# Pedal_SD_USB.net
KiCad netlist of a schematic drawn in Altium Designer
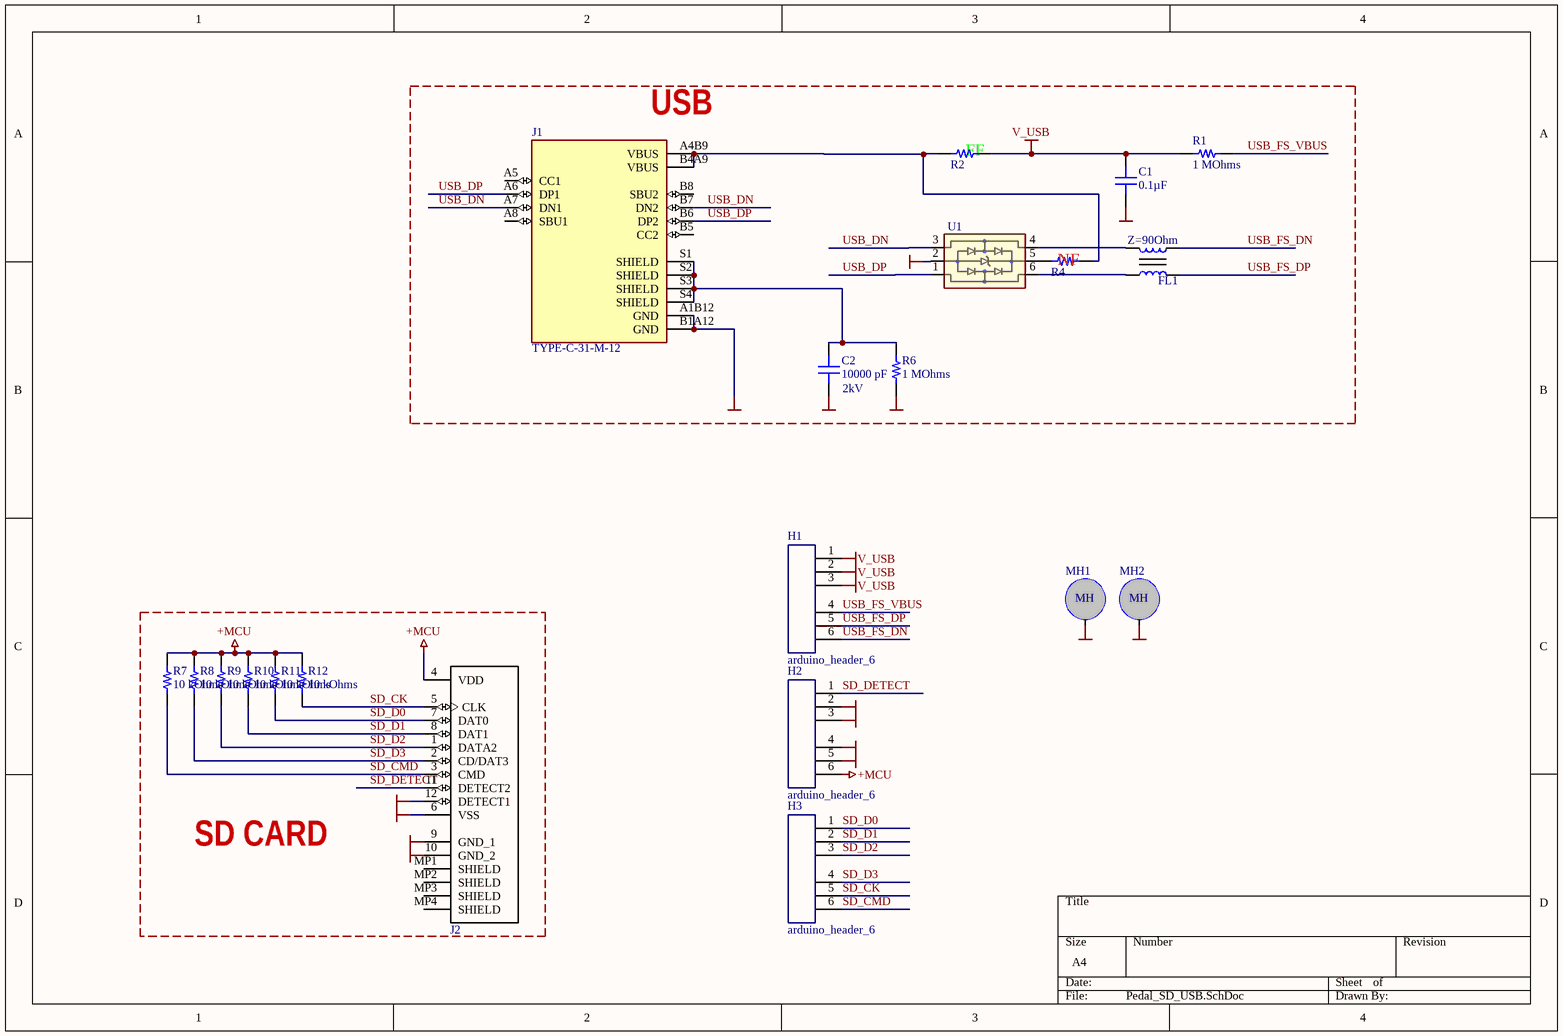
[diagram p0: Pedal_SD_USB.SchDoc]

(export (version "E")
  (design (tool "Eeschema 10.0.6"))
  (components
    (comp (ref "C1")
      (value "0.1µF")
      (footprint "CAP 0402_1005")
      (description "CAP CER 0.1UF 16V X7R 0402")
      (fields (field (name "PART NUMBER") "C0402C104K4RACAUTO") (field (name "MANUFACTURER") "KEMET"))
      (libsource (lib "Celestial Altium Library - altium_library") (part "Capacitor"))
    )
    (comp (ref "C2")
      (value "10000 pF")
      (footprint "CAP 1210_3225 - 1MM")
      (description "CAP CER 10000PF 1KV X7R 1210")
      (fields (field (name "PART NUMBER") "C1210C103KDRAC7800") (field (name "MANUFACTURER") "KEMET"))
      (libsource (lib "Celestial Altium Library - altium_library") (part "Capacitor"))
    )
    (comp (ref "FL1")
      (value "Z=90Ohm")
      (footprint "ProtoStack_H750VBT:FIL_ACM2012-361-2P-T002")
      (description "ACM Series 0805 360 Ohm 220mA 500 mOhm DCR 50 V SMT Common Mode Filter")
      (fields (field (name "MP") "ACM2012-361-2P-T002") (field (name "MF") "TDK"))
      (libsource (lib "ProtoStack_H750VBT") (part "ACM2012-361-2P-T002"))
    )
    (comp (ref "H1")
      (value "arduino_header_6")
      (footprint "ProtoStack_H750VBT:header-6_male")
      (libsource (lib "ProtoStack_H750VBT") (part "arduino_header_6"))
    )
    (comp (ref "H2")
      (value "arduino_header_6")
      (footprint "ProtoStack_H750VBT:header-6_male")
      (libsource (lib "ProtoStack_H750VBT") (part "arduino_header_6"))
    )
    (comp (ref "H3")
      (value "arduino_header_6")
      (footprint "ProtoStack_H750VBT:header-6_male")
      (libsource (lib "ProtoStack_H750VBT") (part "arduino_header_6"))
    )
    (comp (ref "J1")
      (value "TYPE-C-31-M-12")
      (footprint "ProtoStack_H750VBT:HRO_TYPE-C-31-M-12 - REZONIT")
      (description "USB Connectors 24 Receptacle 1 8.94*7.3mm RoHS")
      (fields (field (name "MF") "{'manufacturer': u'HRO Electronics Co., Ltd.'}"))
      (libsource (lib "ProtoStack_H750VBT") (part "TYPE-C-31-M-12"))
    )
    (comp (ref "J2")
      (value "SCHA4B0400")
      (footprint "ProtoStack_H750VBT:SCHA4B0400")
      (description "SD card Connector")
      (fields (field (name "MOUSER PART NUMBER") "688-SCHA4B0400"))
      (libsource (lib "ProtoStack_H750VBT") (part "SCHA4B0400"))
    )
    (comp (ref "MH1")
      (value "MountingHole")
      (footprint "ProtoStack_H750VBT:Hole_2.5mm")
      (libsource (lib "ProtoStack_H750VBT") (part "MountingHole"))
    )
    (comp (ref "MH2")
      (value "MountingHole")
      (footprint "ProtoStack_H750VBT:Hole_2.5mm")
      (libsource (lib "ProtoStack_H750VBT") (part "MountingHole"))
    )
    (comp (ref "R1")
      (value "1 MOhms")
      (footprint "RES 0603_1608")
      (description "RES SMD 1M OHM 1% 1/10W 0603")
      (fields
        (field (name "PART NUMBER") "ERJ-3EKF1004V")
        (field (name "MANUFACTURER") "Panasonic Electronic Components")
      )
      (libsource (lib "Celestial Altium Library - altium_library") (part "Resistor"))
    )
    (comp (ref "R2")
      (value "~")
      (footprint "RES 0603_1608")
      (description "RES SMD 0 OHM JUMPER 1/10W 0603")
      (fields (field (name "PART NUMBER") "RCA06030000ZSEA") (field (name "MANUFACTURER") "Vishay Dale"))
      (libsource (lib "Celestial Altium Library - altium_library") (part "Resistor"))
    )
    (comp (ref "R4")
      (value "~")
      (footprint "RES 0603_1608")
      (description "RES SMD 0 OHM JUMPER 1/10W 0603")
      (fields (field (name "PART NUMBER") "RCA06030000ZSEA") (field (name "MANUFACTURER") "Vishay Dale"))
      (libsource (lib "Celestial Altium Library - altium_library") (part "Resistor"))
    )
    (comp (ref "R6")
      (value "1 MOhms")
      (footprint "RES 0603_1608")
      (description "RES SMD 1M OHM 1% 1/10W 0603")
      (fields
        (field (name "PART NUMBER") "ERJ-3EKF1004V")
        (field (name "MANUFACTURER") "Panasonic Electronic Components")
      )
      (libsource (lib "Celestial Altium Library - altium_library") (part "Resistor"))
    )
    (comp (ref "R7")
      (value "10 kOhms")
      (footprint "RES 0603_1608")
      (description "RES SMD 10K OHM 1% 1/10W 0603")
      (fields
        (field (name "PART NUMBER") "ERJ-3EKF1002V")
        (field (name "MANUFACTURER") "Panasonic Electronic Components")
      )
      (libsource (lib "Celestial Altium Library - altium_library") (part "Resistor"))
    )
    (comp (ref "R8")
      (value "10 kOhms")
      (footprint "RES 0603_1608")
      (description "RES SMD 10K OHM 1% 1/10W 0603")
      (fields
        (field (name "PART NUMBER") "ERJ-3EKF1002V")
        (field (name "MANUFACTURER") "Panasonic Electronic Components")
      )
      (libsource (lib "Celestial Altium Library - altium_library") (part "Resistor"))
    )
    (comp (ref "R9")
      (value "10 kOhms")
      (footprint "RES 0603_1608")
      (description "RES SMD 10K OHM 1% 1/10W 0603")
      (fields
        (field (name "PART NUMBER") "ERJ-3EKF1002V")
        (field (name "MANUFACTURER") "Panasonic Electronic Components")
      )
      (libsource (lib "Celestial Altium Library - altium_library") (part "Resistor"))
    )
    (comp (ref "R10")
      (value "10 kOhms")
      (footprint "RES 0603_1608")
      (description "RES SMD 10K OHM 1% 1/10W 0603")
      (fields
        (field (name "PART NUMBER") "ERJ-3EKF1002V")
        (field (name "MANUFACTURER") "Panasonic Electronic Components")
      )
      (libsource (lib "Celestial Altium Library - altium_library") (part "Resistor"))
    )
    (comp (ref "R11")
      (value "10 kOhms")
      (footprint "RES 0603_1608")
      (description "RES SMD 10K OHM 1% 1/10W 0603")
      (fields
        (field (name "PART NUMBER") "ERJ-3EKF1002V")
        (field (name "MANUFACTURER") "Panasonic Electronic Components")
      )
      (libsource (lib "Celestial Altium Library - altium_library") (part "Resistor"))
    )
    (comp (ref "R12")
      (value "10 kOhms")
      (footprint "RES 0603_1608")
      (description "RES SMD 10K OHM 1% 1/10W 0603")
      (fields
        (field (name "PART NUMBER") "ERJ-3EKF1002V")
        (field (name "MANUFACTURER") "Panasonic Electronic Components")
      )
      (libsource (lib "Celestial Altium Library - altium_library") (part "Resistor"))
    )
    (comp (ref "U1")
      (value "~")
      (footprint "SOT-666")
      (description "Very Low Capacitance Esd Protection")
      (fields (field (name "MP") "USBLC6-2") (field (name "MF") "STMicroelectronics"))
      (libsource (lib "ProtoStack_H750VBT") (part "USBLC6-2"))
    )
  )
  (nets
    (net (code "1") (name "+MCU") (class "Default")
      (node (ref "H2") (pin "6") (pinfunction "6_6") (pintype "passive"))
      (node (ref "J2") (pin "4") (pinfunction "VDD_4") (pintype "power_in"))
      (node (ref "R10") (pin "2") (pinfunction "2_2") (pintype "passive"))
      (node (ref "R11") (pin "2") (pinfunction "2_2") (pintype "passive"))
      (node (ref "R12") (pin "2") (pinfunction "2_2") (pintype "passive"))
      (node (ref "R7") (pin "2") (pinfunction "2_2") (pintype "passive"))
      (node (ref "R8") (pin "2") (pinfunction "2_2") (pintype "passive"))
      (node (ref "R9") (pin "2") (pinfunction "2_2") (pintype "passive"))
    )
    (net (code "2") (name "/SD_CK") (class "Default")
      (node (ref "H3") (pin "5") (pinfunction "5_5") (pintype "passive"))
      (node (ref "J2") (pin "5") (pinfunction "CLK_5") (pintype "bidirectional"))
      (node (ref "R12") (pin "1") (pinfunction "1_1") (pintype "passive"))
    )
    (net (code "3") (name "/SD_CMD") (class "Default")
      (node (ref "H3") (pin "6") (pinfunction "6_6") (pintype "passive"))
      (node (ref "J2") (pin "3") (pinfunction "CMD_3") (pintype "bidirectional"))
      (node (ref "R7") (pin "1") (pinfunction "1_1") (pintype "passive"))
    )
    (net (code "4") (name "/SD_D0") (class "Default")
      (node (ref "H3") (pin "1") (pinfunction "1_1") (pintype "passive"))
      (node (ref "J2") (pin "7") (pinfunction "DAT0_7") (pintype "bidirectional"))
      (node (ref "R11") (pin "1") (pinfunction "1_1") (pintype "passive"))
    )
    (net (code "5") (name "/SD_D1") (class "Default")
      (node (ref "H3") (pin "2") (pinfunction "2_2") (pintype "passive"))
      (node (ref "J2") (pin "8") (pinfunction "DAT1_8") (pintype "bidirectional"))
      (node (ref "R10") (pin "1") (pinfunction "1_1") (pintype "passive"))
    )
    (net (code "6") (name "/SD_D2") (class "Default")
      (node (ref "H3") (pin "3") (pinfunction "3_3") (pintype "passive"))
      (node (ref "J2") (pin "1") (pinfunction "DATA2_1") (pintype "bidirectional"))
      (node (ref "R9") (pin "1") (pinfunction "1_1") (pintype "passive"))
    )
    (net (code "7") (name "/SD_D3") (class "Default")
      (node (ref "H3") (pin "4") (pinfunction "4_4") (pintype "passive"))
      (node (ref "J2") (pin "2") (pinfunction "CD/DAT3_2") (pintype "bidirectional"))
      (node (ref "R8") (pin "1") (pinfunction "1_1") (pintype "passive"))
    )
    (net (code "8") (name "/SD_DETECT") (class "Default")
      (node (ref "H2") (pin "1") (pinfunction "1_1") (pintype "passive"))
      (node (ref "J2") (pin "11") (pinfunction "DETECT2_11") (pintype "bidirectional"))
    )
    (net (code "9") (name "/USB_DN") (class "Default")
      (node (ref "J1") (pin "A7") (pinfunction "DN1_A7") (pintype "bidirectional"))
      (node (ref "J1") (pin "B7") (pinfunction "DN2_B7") (pintype "bidirectional"))
      (node (ref "U1") (pin "3") (pinfunction "3_3") (pintype "bidirectional"))
    )
    (net (code "10") (name "/USB_DP") (class "Default")
      (node (ref "J1") (pin "A6") (pinfunction "DP1_A6") (pintype "bidirectional"))
      (node (ref "J1") (pin "B6") (pinfunction "DP2_B6") (pintype "bidirectional"))
      (node (ref "U1") (pin "1") (pinfunction "1_1") (pintype "bidirectional"))
    )
    (net (code "11") (name "/USB_FS_DN") (class "Default")
      (node (ref "FL1") (pin "3") (pinfunction "3_3") (pintype "passive"))
      (node (ref "H1") (pin "6") (pinfunction "6_6") (pintype "passive"))
    )
    (net (code "12") (name "/USB_FS_DP") (class "Default")
      (node (ref "FL1") (pin "4") (pinfunction "4_4") (pintype "passive"))
      (node (ref "H1") (pin "5") (pinfunction "5_5") (pintype "passive"))
    )
    (net (code "13") (name "/USB_FS_VBUS") (class "Default")
      (node (ref "H1") (pin "4") (pinfunction "4_4") (pintype "passive"))
      (node (ref "R1") (pin "1") (pinfunction "1_1") (pintype "passive"))
    )
    (net (code "14") (name "GND") (class "Default")
      (node (ref "C1") (pin "1") (pinfunction "1_1") (pintype "passive"))
      (node (ref "C2") (pin "1") (pinfunction "1_1") (pintype "passive"))
      (node (ref "H2") (pin "2") (pinfunction "2_2") (pintype "passive"))
      (node (ref "H2") (pin "3") (pinfunction "3_3") (pintype "passive"))
      (node (ref "H2") (pin "4") (pinfunction "4_4") (pintype "passive"))
      (node (ref "H2") (pin "5") (pinfunction "5_5") (pintype "passive"))
      (node (ref "J1") (pin "A1B12") (pinfunction "GND_A1B12") (pintype "power_in"))
      (node (ref "J1") (pin "B1A12") (pinfunction "GND_B1A12") (pintype "power_in"))
      (node (ref "J2") (pin "10") (pinfunction "GND_2_10") (pintype "passive"))
      (node (ref "J2") (pin "12") (pinfunction "DETECT1_12") (pintype "bidirectional"))
      (node (ref "J2") (pin "6") (pinfunction "VSS_6") (pintype "power_in"))
      (node (ref "J2") (pin "9") (pinfunction "GND_1_9") (pintype "passive"))
      (node (ref "MH1") (pin "0") (pinfunction "0_0") (pintype "passive"))
      (node (ref "MH2") (pin "0") (pinfunction "0_0") (pintype "passive"))
      (node (ref "R6") (pin "1") (pinfunction "1_1") (pintype "passive"))
      (node (ref "U1") (pin "2") (pinfunction "2_2") (pintype "power_in"))
    )
    (net (code "15") (name "Net-(C2-Pad2)") (class "Default")
      (node (ref "C2") (pin "2") (pinfunction "2_2") (pintype "passive"))
      (node (ref "J1") (pin "S1") (pinfunction "SHIELD_S1") (pintype "passive"))
      (node (ref "J1") (pin "S2") (pinfunction "SHIELD_S2") (pintype "passive"))
      (node (ref "J1") (pin "S3") (pinfunction "SHIELD_S3") (pintype "passive"))
      (node (ref "J1") (pin "S4") (pinfunction "SHIELD_S4") (pintype "passive"))
      (node (ref "R6") (pin "2") (pinfunction "2_2") (pintype "passive"))
    )
    (net (code "16") (name "Net-(FL1-Pad1)") (class "Default")
      (node (ref "FL1") (pin "1") (pinfunction "1_1") (pintype "passive"))
      (node (ref "U1") (pin "6") (pinfunction "6_6") (pintype "bidirectional"))
    )
    (net (code "17") (name "Net-(FL1-Pad2)") (class "Default")
      (node (ref "FL1") (pin "2") (pinfunction "2_2") (pintype "passive"))
      (node (ref "U1") (pin "4") (pinfunction "4_4") (pintype "bidirectional"))
    )
    (net (code "18") (name "Net-(J1-VBUS-PadA4B9)") (class "Default")
      (node (ref "J1") (pin "A4B9") (pinfunction "VBUS_A4B9") (pintype "power_in"))
      (node (ref "J1") (pin "B4A9") (pinfunction "VBUS_B4A9") (pintype "power_in"))
      (node (ref "R2") (pin "2") (pinfunction "2_2") (pintype "passive"))
      (node (ref "R4") (pin "1") (pinfunction "1_1") (pintype "passive"))
    )
    (net (code "19") (name "Net-(R4-Pad2)") (class "Default")
      (node (ref "R4") (pin "2") (pinfunction "2_2") (pintype "passive"))
      (node (ref "U1") (pin "5") (pinfunction "5_5") (pintype "power_in"))
    )
    (net (code "20") (name "V_USB") (class "Default")
      (node (ref "C1") (pin "2") (pinfunction "2_2") (pintype "passive"))
      (node (ref "H1") (pin "1") (pinfunction "1_1") (pintype "passive"))
      (node (ref "H1") (pin "2") (pinfunction "2_2") (pintype "passive"))
      (node (ref "H1") (pin "3") (pinfunction "3_3") (pintype "passive"))
      (node (ref "R1") (pin "2") (pinfunction "2_2") (pintype "passive"))
      (node (ref "R2") (pin "1") (pinfunction "1_1") (pintype "passive"))
    )
    (net (code "21") (name "unconnected-(J1-CC1-PadA5)") (class "Default")
      (node (ref "J1") (pin "A5") (pinfunction "CC1_A5") (pintype "bidirectional"))
    )
    (net (code "22") (name "unconnected-(J1-CC2-PadB5)") (class "Default")
      (node (ref "J1") (pin "B5") (pinfunction "CC2_B5") (pintype "bidirectional"))
    )
    (net (code "23") (name "unconnected-(J1-SBU1-PadA8)") (class "Default")
      (node (ref "J1") (pin "A8") (pinfunction "SBU1_A8") (pintype "bidirectional"))
    )
    (net (code "24") (name "unconnected-(J1-SBU2-PadB8)") (class "Default")
      (node (ref "J1") (pin "B8") (pinfunction "SBU2_B8") (pintype "bidirectional"))
    )
    (net (code "25") (name "unconnected-(J2-SHIELD-PadMP1)") (class "Default")
      (node (ref "J2") (pin "MP1") (pinfunction "SHIELD_MP1") (pintype "passive"))
    )
    (net (code "26") (name "unconnected-(J2-SHIELD-PadMP2)") (class "Default")
      (node (ref "J2") (pin "MP2") (pinfunction "SHIELD_MP2") (pintype "passive"))
    )
    (net (code "27") (name "unconnected-(J2-SHIELD-PadMP3)") (class "Default")
      (node (ref "J2") (pin "MP3") (pinfunction "SHIELD_MP3") (pintype "passive"))
    )
    (net (code "28") (name "unconnected-(J2-SHIELD-PadMP4)") (class "Default")
      (node (ref "J2") (pin "MP4") (pinfunction "SHIELD_MP4") (pintype "passive"))
    )
  )
)
